# FilterBoard_Schematic.net
KiCad netlist of a schematic drawn in Altium Designer
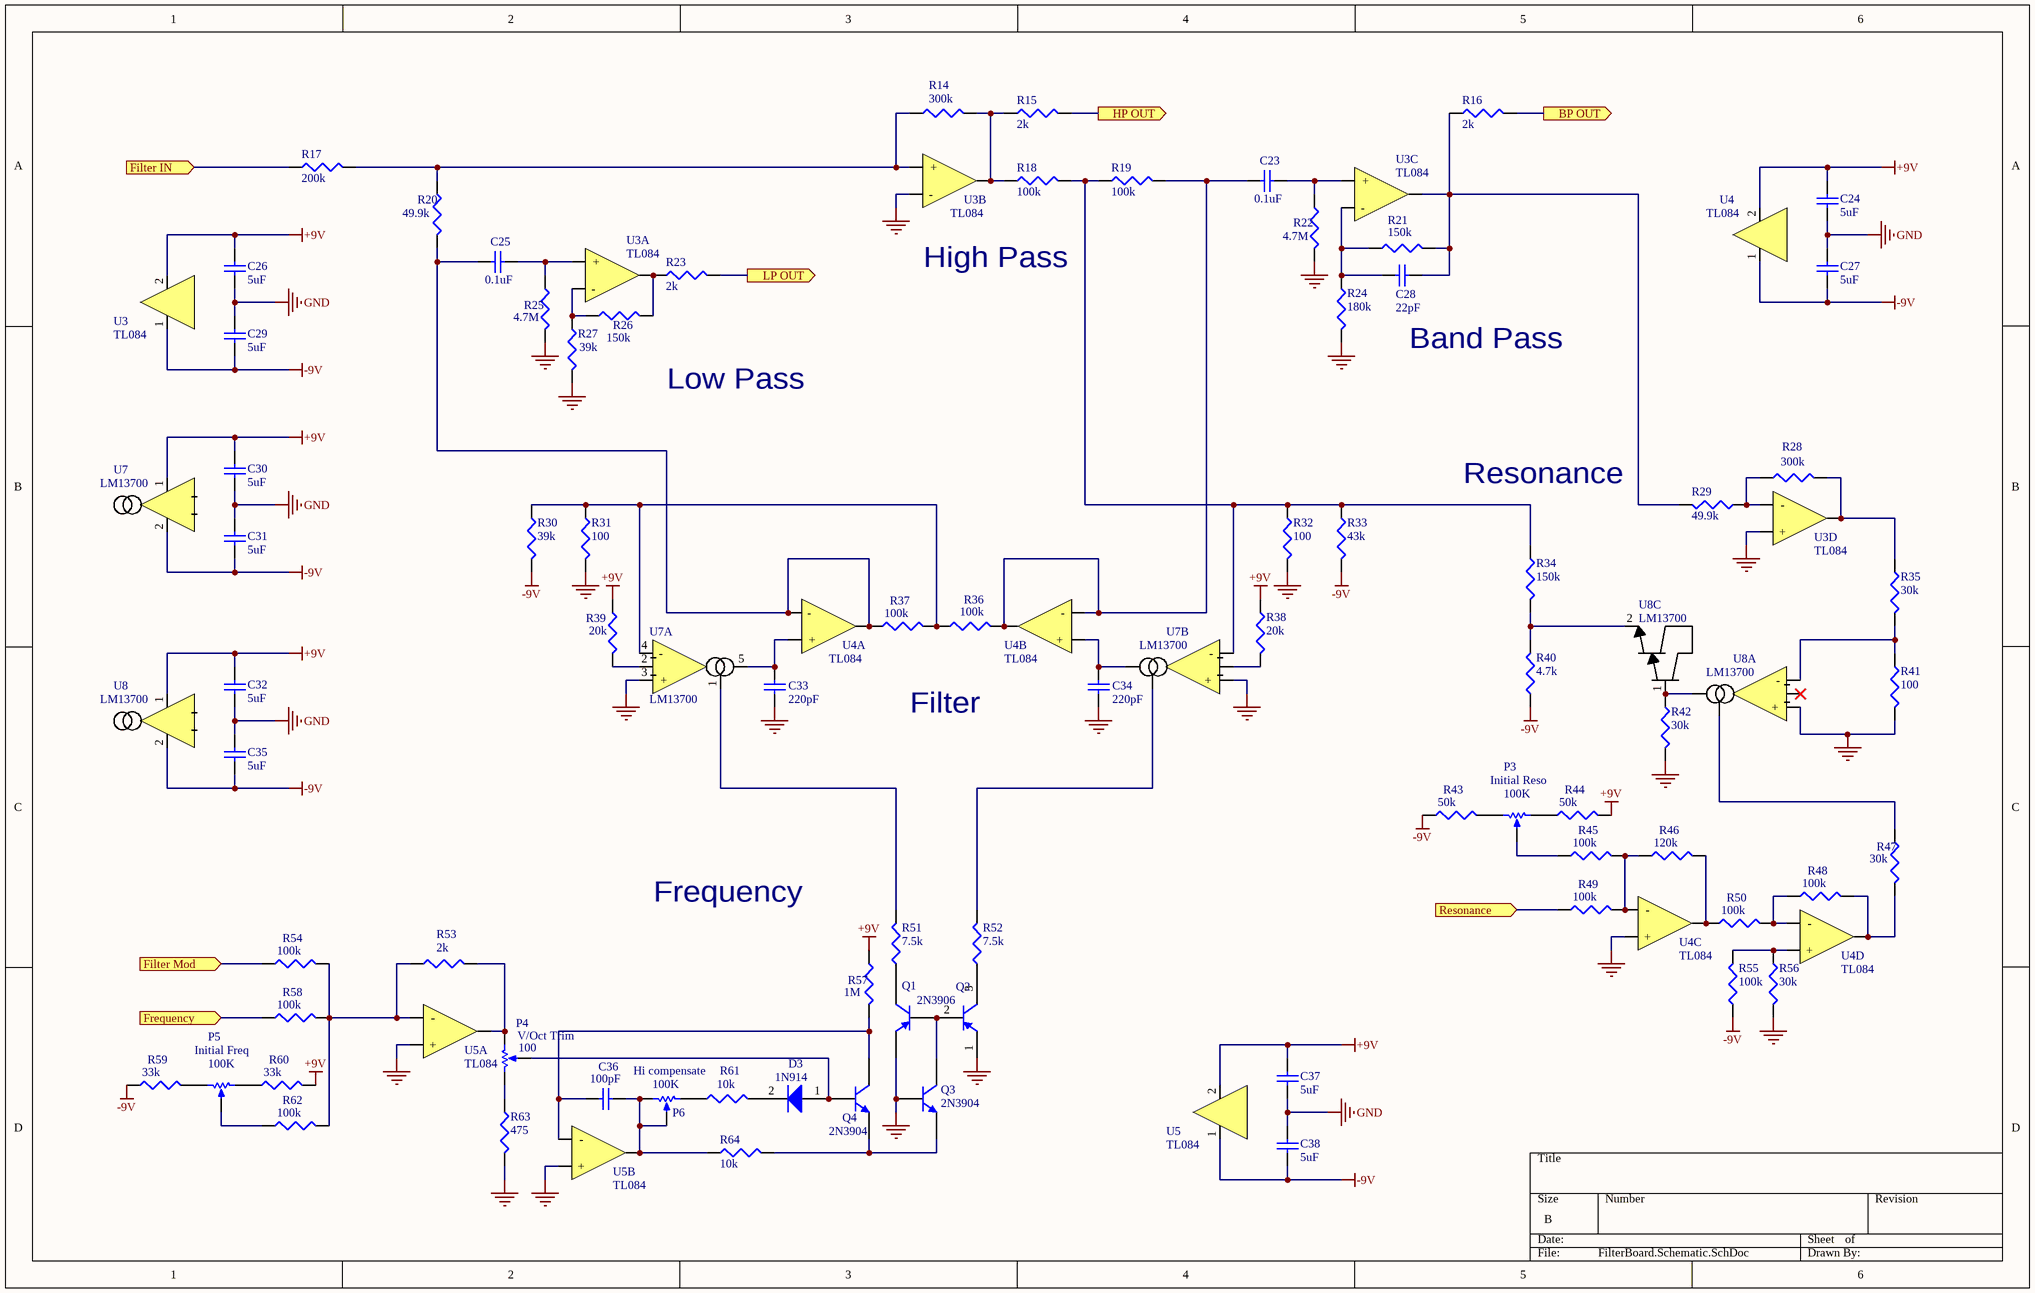
[diagram p0: FilterBoard.Schematic.SchDoc]

(export (version "E")
  (design (tool "Eeschema 10.0.6"))
  (components
    (comp (ref "C23")
      (value "0.1uF")
      (footprint "CAPC1608N - cap")
      (description "Capacitor (Semiconductor SIM Model)")
      (fields (field (name "PUBLISHER") "Altium Limited"))
      (libsource (lib "Miscellaneous Devices") (part "Cap Semi"))
    )
    (comp (ref "C24")
      (value "5uF")
      (footprint "CAPC1608N - cap")
      (description "Capacitor (Semiconductor SIM Model)")
      (fields (field (name "PUBLISHER") "Altium Limited"))
      (libsource (lib "Miscellaneous Devices") (part "Cap Semi"))
    )
    (comp (ref "C25")
      (value "0.1uF")
      (footprint "CAPC1608N - cap")
      (description "Capacitor (Semiconductor SIM Model)")
      (fields (field (name "PUBLISHER") "Altium Limited"))
      (libsource (lib "Miscellaneous Devices") (part "Cap Semi"))
    )
    (comp (ref "C26")
      (value "5uF")
      (footprint "CAPC1608N - cap")
      (description "Capacitor (Semiconductor SIM Model)")
      (fields (field (name "PUBLISHER") "Altium Limited"))
      (libsource (lib "Miscellaneous Devices") (part "Cap Semi"))
    )
    (comp (ref "C27")
      (value "5uF")
      (footprint "CAPC1608N - cap")
      (description "Capacitor (Semiconductor SIM Model)")
      (fields (field (name "PUBLISHER") "Altium Limited"))
      (libsource (lib "Miscellaneous Devices") (part "Cap Semi"))
    )
    (comp (ref "C28")
      (value "22pF")
      (footprint "CAPC1608N - cap")
      (description "Capacitor (Semiconductor SIM Model)")
      (fields (field (name "PUBLISHER") "Altium Limited"))
      (libsource (lib "Miscellaneous Devices") (part "Cap Semi"))
    )
    (comp (ref "C29")
      (value "5uF")
      (footprint "CAPC1608N - cap")
      (description "Capacitor (Semiconductor SIM Model)")
      (fields (field (name "PUBLISHER") "Altium Limited"))
      (libsource (lib "Miscellaneous Devices") (part "Cap Semi"))
    )
    (comp (ref "C30")
      (value "5uF")
      (footprint "CAPC1608N - cap")
      (description "Capacitor (Semiconductor SIM Model)")
      (fields (field (name "PUBLISHER") "Altium Limited"))
      (libsource (lib "Miscellaneous Devices") (part "Cap Semi"))
    )
    (comp (ref "C31")
      (value "5uF")
      (footprint "CAPC1608N - cap")
      (description "Capacitor (Semiconductor SIM Model)")
      (fields (field (name "PUBLISHER") "Altium Limited"))
      (libsource (lib "Miscellaneous Devices") (part "Cap Semi"))
    )
    (comp (ref "C32")
      (value "5uF")
      (footprint "CAPC1608N - cap")
      (description "Capacitor (Semiconductor SIM Model)")
      (fields (field (name "PUBLISHER") "Altium Limited"))
      (libsource (lib "Miscellaneous Devices") (part "Cap Semi"))
    )
    (comp (ref "C33")
      (value "220pF")
      (footprint "CAPC1608N - cap")
      (description "Capacitor (Semiconductor SIM Model)")
      (fields (field (name "PUBLISHER") "Altium Limited"))
      (libsource (lib "Miscellaneous Devices") (part "Cap Semi"))
    )
    (comp (ref "C34")
      (value "220pF")
      (footprint "CAPC1608N - cap")
      (description "Capacitor (Semiconductor SIM Model)")
      (fields (field (name "PUBLISHER") "Altium Limited"))
      (libsource (lib "Miscellaneous Devices") (part "Cap Semi"))
    )
    (comp (ref "C35")
      (value "5uF")
      (footprint "CAPC1608N - cap")
      (description "Capacitor (Semiconductor SIM Model)")
      (fields (field (name "PUBLISHER") "Altium Limited"))
      (libsource (lib "Miscellaneous Devices") (part "Cap Semi"))
    )
    (comp (ref "C36")
      (value "100pF")
      (footprint "CAPC1608N - cap")
      (description "Capacitor (Semiconductor SIM Model)")
      (fields (field (name "PUBLISHER") "Altium Limited"))
      (libsource (lib "Miscellaneous Devices") (part "Cap Semi"))
    )
    (comp (ref "C37")
      (value "5uF")
      (footprint "CAPC1608N - cap")
      (description "Capacitor (Semiconductor SIM Model)")
      (fields (field (name "PUBLISHER") "Altium Limited"))
      (libsource (lib "Miscellaneous Devices") (part "Cap Semi"))
    )
    (comp (ref "C38")
      (value "5uF")
      (footprint "CAPC1608N - cap")
      (description "Capacitor (Semiconductor SIM Model)")
      (fields (field (name "PUBLISHER") "Altium Limited"))
      (libsource (lib "Miscellaneous Devices") (part "Cap Semi"))
    )
    (comp (ref "D3")
      (value "1N914")
      (footprint "1N914")
      (description "1 Amp General Purpose Rectifier")
      (fields (field (name "PUBLISHER") "Altium Limited"))
      (libsource (lib "Miscellaneous Devices") (part "Diode 1N4001"))
    )
    (comp (ref "P3")
      (value "Initial Reso")
      (footprint "BOURNS Trim pot")
      (description "Potentiometer")
      (fields (field (name "ALTIUM_VALUE") "100K") (field (name "PUBLISHER") "Altium Limited"))
      (libsource (lib "Miscellaneous Devices") (part "RPot"))
    )
    (comp (ref "P4")
      (value "V/Oct Trim")
      (footprint "BOURNS Trim pot")
      (description "Potentiometer")
      (fields (field (name "ALTIUM_VALUE") "100") (field (name "PUBLISHER") "Altium Limited"))
      (libsource (lib "Miscellaneous Devices") (part "RPot"))
    )
    (comp (ref "P5")
      (value "Initial Freq")
      (footprint "BOURNS Trim pot")
      (description "Potentiometer")
      (fields (field (name "ALTIUM_VALUE") "100K") (field (name "PUBLISHER") "Altium Limited"))
      (libsource (lib "Miscellaneous Devices") (part "RPot"))
    )
    (comp (ref "P6")
      (value "Hi compensate")
      (footprint "BOURNS Trim pot")
      (description "Potentiometer")
      (fields (field (name "ALTIUM_VALUE") "100K") (field (name "PUBLISHER") "Altium Limited"))
      (libsource (lib "Miscellaneous Devices") (part "RPot"))
    )
    (comp (ref "Q1")
      (value "2N3906")
      (footprint "2N3906")
      (description "PNP General Purpose Amplifier")
      (fields (field (name "PUBLISHER") "Altium Limited"))
      (libsource (lib "") (part "2N3906_1"))
    )
    (comp (ref "Q2")
      (value "2N3906")
      (footprint "2N3906")
      (description "PNP General Purpose Amplifier")
      (fields (field (name "PUBLISHER") "Altium Limited"))
      (libsource (lib "Miscellaneous Devices") (part "2N3906"))
    )
    (comp (ref "Q3")
      (value "2N3904")
      (footprint "2N3906")
      (description "NPN General Purpose Amplifier")
      (fields (field (name "PUBLISHER") "Altium Limited"))
      (libsource (lib "Miscellaneous Devices") (part "2N3904"))
    )
    (comp (ref "Q4")
      (value "2N3904")
      (footprint "2N3906")
      (description "NPN General Purpose Amplifier")
      (fields (field (name "PUBLISHER") "Altium Limited"))
      (libsource (lib "Miscellaneous Devices") (part "2N3904"))
    )
    (comp (ref "R14")
      (value "300k")
      (footprint "CAPC1608N")
      (description "Resistor")
      (fields (field (name "PUBLISHER") "Altium Limited"))
      (libsource (lib "Miscellaneous Devices") (part "Res3"))
    )
    (comp (ref "R15")
      (value "2k")
      (footprint "CAPC1608N")
      (description "Resistor")
      (fields (field (name "PUBLISHER") "Altium Limited"))
      (libsource (lib "Miscellaneous Devices") (part "Res3"))
    )
    (comp (ref "R16")
      (value "2k")
      (footprint "CAPC1608N")
      (description "Resistor")
      (fields (field (name "PUBLISHER") "Altium Limited"))
      (libsource (lib "Miscellaneous Devices") (part "Res3"))
    )
    (comp (ref "R17")
      (value "200k")
      (footprint "CAPC1608N")
      (description "Resistor")
      (fields (field (name "PUBLISHER") "Altium Limited"))
      (libsource (lib "Miscellaneous Devices") (part "Res3"))
    )
    (comp (ref "R18")
      (value "100k")
      (footprint "CAPC1608N")
      (description "Resistor")
      (fields (field (name "PUBLISHER") "Altium Limited"))
      (libsource (lib "Miscellaneous Devices") (part "Res3"))
    )
    (comp (ref "R19")
      (value "100k")
      (footprint "CAPC1608N")
      (description "Resistor")
      (fields (field (name "PUBLISHER") "Altium Limited"))
      (libsource (lib "Miscellaneous Devices") (part "Res3"))
    )
    (comp (ref "R20")
      (value "49.9k")
      (footprint "CAPC1608N")
      (description "Resistor")
      (fields (field (name "PUBLISHER") "Altium Limited"))
      (libsource (lib "Miscellaneous Devices") (part "Res3"))
    )
    (comp (ref "R21")
      (value "150k")
      (footprint "CAPC1608N")
      (description "Resistor")
      (fields (field (name "PUBLISHER") "Altium Limited"))
      (libsource (lib "Miscellaneous Devices") (part "Res3"))
    )
    (comp (ref "R22")
      (value "4.7M")
      (footprint "CAPC1608N")
      (description "Resistor")
      (fields (field (name "PUBLISHER") "Altium Limited"))
      (libsource (lib "Miscellaneous Devices") (part "Res3"))
    )
    (comp (ref "R23")
      (value "2k")
      (footprint "CAPC1608N")
      (description "Resistor")
      (fields (field (name "PUBLISHER") "Altium Limited"))
      (libsource (lib "Miscellaneous Devices") (part "Res3"))
    )
    (comp (ref "R24")
      (value "180k")
      (footprint "CAPC1608N")
      (description "Resistor")
      (fields (field (name "PUBLISHER") "Altium Limited"))
      (libsource (lib "Miscellaneous Devices") (part "Res3"))
    )
    (comp (ref "R25")
      (value "4.7M")
      (footprint "CAPC1608N")
      (description "Resistor")
      (fields (field (name "PUBLISHER") "Altium Limited"))
      (libsource (lib "Miscellaneous Devices") (part "Res3"))
    )
    (comp (ref "R26")
      (value "150k")
      (footprint "CAPC1608N")
      (description "Resistor")
      (fields (field (name "PUBLISHER") "Altium Limited"))
      (libsource (lib "Miscellaneous Devices") (part "Res3"))
    )
    (comp (ref "R27")
      (value "39k")
      (footprint "CAPC1608N")
      (description "Resistor")
      (fields (field (name "PUBLISHER") "Altium Limited"))
      (libsource (lib "Miscellaneous Devices") (part "Res3"))
    )
    (comp (ref "R28")
      (value "300k")
      (footprint "CAPC1608N")
      (description "Resistor")
      (fields (field (name "PUBLISHER") "Altium Limited"))
      (libsource (lib "Miscellaneous Devices") (part "Res3"))
    )
    (comp (ref "R29")
      (value "49.9k")
      (footprint "CAPC1608N")
      (description "Resistor")
      (fields (field (name "PUBLISHER") "Altium Limited"))
      (libsource (lib "Miscellaneous Devices") (part "Res3"))
    )
    (comp (ref "R30")
      (value "39k")
      (footprint "CAPC1608N")
      (description "Resistor")
      (fields (field (name "PUBLISHER") "Altium Limited"))
      (libsource (lib "Miscellaneous Devices") (part "Res3"))
    )
    (comp (ref "R31")
      (value "100")
      (footprint "CAPC1608N")
      (description "Resistor")
      (fields (field (name "PUBLISHER") "Altium Limited"))
      (libsource (lib "Miscellaneous Devices") (part "Res3"))
    )
    (comp (ref "R32")
      (value "100")
      (footprint "CAPC1608N")
      (description "Resistor")
      (fields (field (name "PUBLISHER") "Altium Limited"))
      (libsource (lib "Miscellaneous Devices") (part "Res3"))
    )
    (comp (ref "R33")
      (value "43k")
      (footprint "CAPC1608N")
      (description "Resistor")
      (fields (field (name "PUBLISHER") "Altium Limited"))
      (libsource (lib "Miscellaneous Devices") (part "Res3"))
    )
    (comp (ref "R34")
      (value "150k")
      (footprint "CAPC1608N")
      (description "Resistor")
      (fields (field (name "PUBLISHER") "Altium Limited"))
      (libsource (lib "Miscellaneous Devices") (part "Res3"))
    )
    (comp (ref "R35")
      (value "30k")
      (footprint "CAPC1608N")
      (description "Resistor")
      (fields (field (name "PUBLISHER") "Altium Limited"))
      (libsource (lib "Miscellaneous Devices") (part "Res3"))
    )
    (comp (ref "R36")
      (value "100k")
      (footprint "CAPC1608N")
      (description "Resistor")
      (fields (field (name "PUBLISHER") "Altium Limited"))
      (libsource (lib "Miscellaneous Devices") (part "Res3"))
    )
    (comp (ref "R37")
      (value "100k")
      (footprint "CAPC1608N")
      (description "Resistor")
      (fields (field (name "PUBLISHER") "Altium Limited"))
      (libsource (lib "Miscellaneous Devices") (part "Res3"))
    )
    (comp (ref "R38")
      (value "20k")
      (footprint "CAPC1608N")
      (description "Resistor")
      (fields (field (name "PUBLISHER") "Altium Limited"))
      (libsource (lib "Miscellaneous Devices") (part "Res3"))
    )
    (comp (ref "R39")
      (value "20k")
      (footprint "CAPC1608N")
      (description "Resistor")
      (fields (field (name "PUBLISHER") "Altium Limited"))
      (libsource (lib "Miscellaneous Devices") (part "Res3"))
    )
    (comp (ref "R40")
      (value "4.7k")
      (footprint "CAPC1608N")
      (description "Resistor")
      (fields (field (name "PUBLISHER") "Altium Limited"))
      (libsource (lib "Miscellaneous Devices") (part "Res3"))
    )
    (comp (ref "R41")
      (value "100")
      (footprint "CAPC1608N")
      (description "Resistor")
      (fields (field (name "PUBLISHER") "Altium Limited"))
      (libsource (lib "Miscellaneous Devices") (part "Res3"))
    )
    (comp (ref "R42")
      (value "30k")
      (footprint "CAPC1608N")
      (description "Resistor")
      (fields (field (name "PUBLISHER") "Altium Limited"))
      (libsource (lib "Miscellaneous Devices") (part "Res3"))
    )
    (comp (ref "R43")
      (value "50k")
      (footprint "CAPC1608N")
      (description "Resistor")
      (fields (field (name "PUBLISHER") "Altium Limited"))
      (libsource (lib "Miscellaneous Devices") (part "Res3"))
    )
    (comp (ref "R44")
      (value "50k")
      (footprint "CAPC1608N")
      (description "Resistor")
      (fields (field (name "PUBLISHER") "Altium Limited"))
      (libsource (lib "Miscellaneous Devices") (part "Res3"))
    )
    (comp (ref "R45")
      (value "100k")
      (footprint "CAPC1608N")
      (description "Resistor")
      (fields (field (name "PUBLISHER") "Altium Limited"))
      (libsource (lib "Miscellaneous Devices") (part "Res3"))
    )
    (comp (ref "R46")
      (value "120k")
      (footprint "CAPC1608N")
      (description "Resistor")
      (fields (field (name "PUBLISHER") "Altium Limited"))
      (libsource (lib "Miscellaneous Devices") (part "Res3"))
    )
    (comp (ref "R47")
      (value "30k")
      (footprint "CAPC1608N")
      (description "Resistor")
      (fields (field (name "PUBLISHER") "Altium Limited"))
      (libsource (lib "Miscellaneous Devices") (part "Res3"))
    )
    (comp (ref "R48")
      (value "100k")
      (footprint "CAPC1608N")
      (description "Resistor")
      (fields (field (name "PUBLISHER") "Altium Limited"))
      (libsource (lib "Miscellaneous Devices") (part "Res3"))
    )
    (comp (ref "R49")
      (value "100k")
      (footprint "CAPC1608N")
      (description "Resistor")
      (fields (field (name "PUBLISHER") "Altium Limited"))
      (libsource (lib "Miscellaneous Devices") (part "Res3"))
    )
    (comp (ref "R50")
      (value "100k")
      (footprint "CAPC1608N")
      (description "Resistor")
      (fields (field (name "PUBLISHER") "Altium Limited"))
      (libsource (lib "Miscellaneous Devices") (part "Res3"))
    )
    (comp (ref "R51")
      (value "7.5k")
      (footprint "CAPC1608N")
      (description "Resistor")
      (fields (field (name "PUBLISHER") "Altium Limited"))
      (libsource (lib "Miscellaneous Devices") (part "Res3"))
    )
    (comp (ref "R52")
      (value "7.5k")
      (footprint "CAPC1608N")
      (description "Resistor")
      (fields (field (name "PUBLISHER") "Altium Limited"))
      (libsource (lib "Miscellaneous Devices") (part "Res3"))
    )
    (comp (ref "R53")
      (value "2k")
      (footprint "CAPC1608N")
      (description "Resistor")
      (fields (field (name "PUBLISHER") "Altium Limited"))
      (libsource (lib "Miscellaneous Devices") (part "Res3"))
    )
    (comp (ref "R54")
      (value "100k")
      (footprint "CAPC1608N")
      (description "Resistor")
      (fields (field (name "PUBLISHER") "Altium Limited"))
      (libsource (lib "Miscellaneous Devices") (part "Res3"))
    )
    (comp (ref "R55")
      (value "100k")
      (footprint "CAPC1608N")
      (description "Resistor")
      (fields (field (name "PUBLISHER") "Altium Limited"))
      (libsource (lib "Miscellaneous Devices") (part "Res3"))
    )
    (comp (ref "R56")
      (value "30k")
      (footprint "CAPC1608N")
      (description "Resistor")
      (fields (field (name "PUBLISHER") "Altium Limited"))
      (libsource (lib "Miscellaneous Devices") (part "Res3"))
    )
    (comp (ref "R57")
      (value "1M")
      (footprint "CAPC1608N")
      (description "Resistor")
      (fields (field (name "PUBLISHER") "Altium Limited"))
      (libsource (lib "Miscellaneous Devices") (part "Res3"))
    )
    (comp (ref "R58")
      (value "100k")
      (footprint "CAPC1608N")
      (description "Resistor")
      (fields (field (name "PUBLISHER") "Altium Limited"))
      (libsource (lib "Miscellaneous Devices") (part "Res3"))
    )
    (comp (ref "R59")
      (value "33k")
      (footprint "CAPC1608N")
      (description "Resistor")
      (fields (field (name "PUBLISHER") "Altium Limited"))
      (libsource (lib "Miscellaneous Devices") (part "Res3"))
    )
    (comp (ref "R60")
      (value "33k")
      (footprint "CAPC1608N")
      (description "Resistor")
      (fields (field (name "PUBLISHER") "Altium Limited"))
      (libsource (lib "Miscellaneous Devices") (part "Res3"))
    )
    (comp (ref "R61")
      (value "10k")
      (footprint "CAPC1608N")
      (description "Resistor")
      (fields (field (name "PUBLISHER") "Altium Limited"))
      (libsource (lib "Miscellaneous Devices") (part "Res3"))
    )
    (comp (ref "R62")
      (value "100k")
      (footprint "CAPC1608N")
      (description "Resistor")
      (fields (field (name "PUBLISHER") "Altium Limited"))
      (libsource (lib "Miscellaneous Devices") (part "Res3"))
    )
    (comp (ref "R63")
      (value "475")
      (footprint "CAPC1608N")
      (description "Resistor")
      (fields (field (name "PUBLISHER") "Altium Limited"))
      (libsource (lib "Miscellaneous Devices") (part "Res3"))
    )
    (comp (ref "R64")
      (value "10k")
      (footprint "CAPC1608N")
      (description "Resistor")
      (fields (field (name "PUBLISHER") "Altium Limited"))
      (libsource (lib "Miscellaneous Devices") (part "Res3"))
    )
    (comp (ref "U3")
      (value "TL084")
      (footprint "TL084 - Alim")
      (libsource (lib "SynthyTwo.Components") (part "TL_CLEAN"))
    )
    (comp (ref "U3A") (value "TL084") (footprint "TL084 - 3pads") (libsource (lib "") (part "TL084_1")))
    (comp (ref "U3B") (value "TL084") (footprint "TL084 - 3pads") (libsource (lib "") (part "TL084_1")))
    (comp (ref "U3C") (value "TL084") (footprint "TL084 - 3pads") (libsource (lib "") (part "TL084_1")))
    (comp (ref "U3D")
      (value "TL084")
      (footprint "TL084 - 3pads")
      (libsource (lib "SynthyTwo.Components") (part "TL084"))
    )
    (comp (ref "U4")
      (value "TL084")
      (footprint "TL084 - Alim")
      (libsource (lib "SynthyTwo.Components") (part "TL_CLEAN"))
    )
    (comp (ref "U4A") (value "TL084") (footprint "TL084 - 3pads") (libsource (lib "") (part "TL084_1")))
    (comp (ref "U4B") (value "TL084") (footprint "TL084 - 3pads") (libsource (lib "") (part "TL084_1")))
    (comp (ref "U4C")
      (value "TL084")
      (footprint "TL084 - 3pads")
      (libsource (lib "SynthyTwo.Components") (part "TL084"))
    )
    (comp (ref "U4D")
      (value "TL084")
      (footprint "TL084 - 3pads")
      (libsource (lib "SynthyTwo.Components") (part "TL084"))
    )
    (comp (ref "U5")
      (value "TL084")
      (footprint "TL084 - Alim")
      (libsource (lib "SynthyTwo.Components") (part "TL_CLEAN"))
    )
    (comp (ref "U5A")
      (value "TL084")
      (footprint "TL084 - 3pads")
      (libsource (lib "SynthyTwo.Components") (part "TL084"))
    )
    (comp (ref "U5B")
      (value "TL084")
      (footprint "TL084 - 3pads")
      (libsource (lib "SynthyTwo.Components") (part "TL084"))
    )
    (comp (ref "U7")
      (value "LM13700")
      (footprint "LM13700 - Alim")
      (libsource (lib "SynthyTwo.Components") (part "LM13700"))
    )
    (comp (ref "U7A")
      (value "LM13700")
      (footprint "LM13700 - A")
      (libsource (lib "SynthyTwo.Components") (part "LM13700_2"))
    )
    (comp (ref "U7B") (value "LM13700") (footprint "LM13700 - B") (libsource (lib "") (part "LM13700_2_1")))
    (comp (ref "U8")
      (value "LM13700")
      (footprint "LM13700 - Alim")
      (libsource (lib "SynthyTwo.Components") (part "LM13700"))
    )
    (comp (ref "U8A") (value "LM13700") (footprint "LM13700 - A") (libsource (lib "") (part "LM13700_2_1")))
    (comp (ref "U8C")
      (value "LM13700")
      (footprint "LM13700 - C")
      (libsource (lib "SynthyTwo.Components") (part "LM13700_1"))
    )
  )
  (nets
    (net (code "1") (name "+9V") (class "Default")
      (node (ref "C24") (pin "1") (pinfunction "1_1") (pintype "passive"))
      (node (ref "C26") (pin "1") (pinfunction "1_1") (pintype "passive"))
      (node (ref "C30") (pin "1") (pinfunction "1_1") (pintype "passive"))
      (node (ref "C32") (pin "1") (pinfunction "1_1") (pintype "passive"))
      (node (ref "C37") (pin "1") (pinfunction "1_1") (pintype "passive"))
      (node (ref "R38") (pin "1") (pinfunction "1_1") (pintype "passive"))
      (node (ref "R39") (pin "1") (pinfunction "1_1") (pintype "passive"))
      (node (ref "R44") (pin "2") (pinfunction "2_2") (pintype "passive"))
      (node (ref "R57") (pin "1") (pinfunction "1_1") (pintype "passive"))
      (node (ref "R60") (pin "2") (pinfunction "2_2") (pintype "passive"))
      (node (ref "U3") (pin "2") (pinfunction "VCC-_2") (pintype "passive"))
      (node (ref "U4") (pin "2") (pinfunction "VCC-_2") (pintype "passive"))
      (node (ref "U5") (pin "2") (pinfunction "VCC-_2") (pintype "passive"))
      (node (ref "U7") (pin "1") (pinfunction "VCC-_1") (pintype "passive"))
      (node (ref "U8") (pin "1") (pinfunction "VCC-_1") (pintype "passive"))
    )
    (net (code "2") (name "-9V") (class "Default")
      (node (ref "C27") (pin "2") (pinfunction "2_2") (pintype "passive"))
      (node (ref "C29") (pin "2") (pinfunction "2_2") (pintype "passive"))
      (node (ref "C31") (pin "2") (pinfunction "2_2") (pintype "passive"))
      (node (ref "C35") (pin "2") (pinfunction "2_2") (pintype "passive"))
      (node (ref "C38") (pin "2") (pinfunction "2_2") (pintype "passive"))
      (node (ref "R30") (pin "2") (pinfunction "2_2") (pintype "passive"))
      (node (ref "R33") (pin "2") (pinfunction "2_2") (pintype "passive"))
      (node (ref "R40") (pin "1") (pinfunction "1_1") (pintype "passive"))
      (node (ref "R43") (pin "1") (pinfunction "1_1") (pintype "passive"))
      (node (ref "R55") (pin "1") (pinfunction "1_1") (pintype "passive"))
      (node (ref "R59") (pin "1") (pinfunction "1_1") (pintype "passive"))
      (node (ref "U3") (pin "1") (pinfunction "VCC+_1") (pintype "passive"))
      (node (ref "U4") (pin "1") (pinfunction "VCC+_1") (pintype "passive"))
      (node (ref "U5") (pin "1") (pinfunction "VCC+_1") (pintype "passive"))
      (node (ref "U7") (pin "2") (pinfunction "VCC-_2") (pintype "passive"))
      (node (ref "U8") (pin "2") (pinfunction "VCC-_2") (pintype "passive"))
    )
    (net (code "3") (name "/BP OUT") (class "Default")
      (node (ref "R16") (pin "2") (pinfunction "2_2") (pintype "passive"))
    )
    (net (code "4") (name "/Filter IN") (class "Default")
      (node (ref "R17") (pin "1") (pinfunction "1_1") (pintype "passive"))
    )
    (net (code "5") (name "/Filter Mod") (class "Default")
      (node (ref "R54") (pin "1") (pinfunction "1_1") (pintype "passive"))
    )
    (net (code "6") (name "/Frequency") (class "Default")
      (node (ref "R58") (pin "1") (pinfunction "1_1") (pintype "passive"))
    )
    (net (code "7") (name "/HP OUT") (class "Default")
      (node (ref "R15") (pin "2") (pinfunction "2_2") (pintype "passive"))
    )
    (net (code "8") (name "/LP OUT") (class "Default")
      (node (ref "R23") (pin "2") (pinfunction "2_2") (pintype "passive"))
    )
    (net (code "9") (name "/Resonance") (class "Default")
      (node (ref "R49") (pin "1") (pinfunction "1_1") (pintype "passive"))
    )
    (net (code "10") (name "GND") (class "Default")
      (node (ref "C24") (pin "2") (pinfunction "2_2") (pintype "passive"))
      (node (ref "C26") (pin "2") (pinfunction "2_2") (pintype "passive"))
      (node (ref "C27") (pin "1") (pinfunction "1_1") (pintype "passive"))
      (node (ref "C29") (pin "1") (pinfunction "1_1") (pintype "passive"))
      (node (ref "C30") (pin "2") (pinfunction "2_2") (pintype "passive"))
      (node (ref "C31") (pin "1") (pinfunction "1_1") (pintype "passive"))
      (node (ref "C32") (pin "2") (pinfunction "2_2") (pintype "passive"))
      (node (ref "C33") (pin "1") (pinfunction "1_1") (pintype "passive"))
      (node (ref "C34") (pin "1") (pinfunction "1_1") (pintype "passive"))
      (node (ref "C35") (pin "1") (pinfunction "1_1") (pintype "passive"))
      (node (ref "C37") (pin "2") (pinfunction "2_2") (pintype "passive"))
      (node (ref "C38") (pin "1") (pinfunction "1_1") (pintype "passive"))
      (node (ref "Q1") (pin "1") (pinfunction "E_1") (pintype "passive"))
      (node (ref "Q2") (pin "1") (pinfunction "E_1") (pintype "passive"))
      (node (ref "Q3") (pin "2") (pinfunction "B_2") (pintype "passive"))
      (node (ref "R22") (pin "2") (pinfunction "2_2") (pintype "passive"))
      (node (ref "R24") (pin "2") (pinfunction "2_2") (pintype "passive"))
      (node (ref "R25") (pin "2") (pinfunction "2_2") (pintype "passive"))
      (node (ref "R27") (pin "2") (pinfunction "2_2") (pintype "passive"))
      (node (ref "R31") (pin "2") (pinfunction "2_2") (pintype "passive"))
      (node (ref "R32") (pin "2") (pinfunction "2_2") (pintype "passive"))
      (node (ref "R41") (pin "2") (pinfunction "2_2") (pintype "passive"))
      (node (ref "R42") (pin "2") (pinfunction "2_2") (pintype "passive"))
      (node (ref "R56") (pin "2") (pinfunction "2_2") (pintype "passive"))
      (node (ref "R63") (pin "2") (pinfunction "2_2") (pintype "passive"))
      (node (ref "U3B") (pin "2") (pinfunction "-_2") (pintype "passive"))
      (node (ref "U3D") (pin "3") (pinfunction "+_3") (pintype "passive"))
      (node (ref "U4C") (pin "3") (pinfunction "+_3") (pintype "passive"))
      (node (ref "U5A") (pin "3") (pinfunction "+_3") (pintype "passive"))
      (node (ref "U5B") (pin "3") (pinfunction "+_3") (pintype "passive"))
      (node (ref "U7A") (pin "3") (pinfunction "+_3") (pintype "passive"))
      (node (ref "U7B") (pin "3") (pinfunction "+_3") (pintype "passive"))
      (node (ref "U8A") (pin "3") (pinfunction "+_3") (pintype "passive"))
    )
    (net (code "11") (name "Net-(D3-A)") (class "Default")
      (node (ref "D3") (pin "1") (pinfunction "A_1") (pintype "passive"))
      (node (ref "P4") (pin "3") (pinfunction "TAP_3") (pintype "passive"))
      (node (ref "Q4") (pin "2") (pinfunction "B_2") (pintype "passive"))
    )
    (net (code "12") (name "Net-(D3-K)") (class "Default")
      (node (ref "D3") (pin "2") (pinfunction "K_2") (pintype "passive"))
      (node (ref "R61") (pin "2") (pinfunction "2_2") (pintype "passive"))
    )
    (net (code "13") (name "Net-(P3-BOT)") (class "Default")
      (node (ref "P3") (pin "2") (pinfunction "BOT_2") (pintype "passive"))
      (node (ref "R43") (pin "2") (pinfunction "2_2") (pintype "passive"))
    )
    (net (code "14") (name "Net-(P3-TAP)") (class "Default")
      (node (ref "P3") (pin "3") (pinfunction "TAP_3") (pintype "passive"))
      (node (ref "R45") (pin "1") (pinfunction "1_1") (pintype "passive"))
    )
    (net (code "15") (name "Net-(P3-TOP)") (class "Default")
      (node (ref "P3") (pin "1") (pinfunction "TOP_1") (pintype "passive"))
      (node (ref "R44") (pin "1") (pinfunction "1_1") (pintype "passive"))
    )
    (net (code "16") (name "Net-(P4-BOT)") (class "Default")
      (node (ref "P4") (pin "2") (pinfunction "BOT_2") (pintype "passive"))
      (node (ref "R63") (pin "1") (pinfunction "1_1") (pintype "passive"))
    )
    (net (code "17") (name "Net-(P4-TOP)") (class "Default")
      (node (ref "P4") (pin "1") (pinfunction "TOP_1") (pintype "passive"))
      (node (ref "R53") (pin "2") (pinfunction "2_2") (pintype "passive"))
      (node (ref "U5A") (pin "1") (pinfunction "OUT_1") (pintype "passive"))
    )
    (net (code "18") (name "Net-(P5-BOT)") (class "Default")
      (node (ref "P5") (pin "2") (pinfunction "BOT_2") (pintype "passive"))
      (node (ref "R59") (pin "2") (pinfunction "2_2") (pintype "passive"))
    )
    (net (code "19") (name "Net-(P5-TAP)") (class "Default")
      (node (ref "P5") (pin "3") (pinfunction "TAP_3") (pintype "passive"))
      (node (ref "R62") (pin "1") (pinfunction "1_1") (pintype "passive"))
    )
    (net (code "20") (name "Net-(P5-TOP)") (class "Default")
      (node (ref "P5") (pin "1") (pinfunction "TOP_1") (pintype "passive"))
      (node (ref "R60") (pin "1") (pinfunction "1_1") (pintype "passive"))
    )
    (net (code "21") (name "Net-(P6-BOT)") (class "Default")
      (node (ref "C36") (pin "2") (pinfunction "2_2") (pintype "passive"))
      (node (ref "P6") (pin "2") (pinfunction "BOT_2") (pintype "passive"))
      (node (ref "P6") (pin "3") (pinfunction "TAP_3") (pintype "passive"))
      (node (ref "R64") (pin "1") (pinfunction "1_1") (pintype "passive"))
      (node (ref "U5B") (pin "1") (pinfunction "OUT_1") (pintype "passive"))
    )
    (net (code "22") (name "Net-(P6-TOP)") (class "Default")
      (node (ref "P6") (pin "1") (pinfunction "TOP_1") (pintype "passive"))
      (node (ref "R61") (pin "1") (pinfunction "1_1") (pintype "passive"))
    )
    (net (code "23") (name "Net-(Q1-B)") (class "Default")
      (node (ref "Q1") (pin "2") (pinfunction "B_2") (pintype "passive"))
      (node (ref "Q2") (pin "2") (pinfunction "B_2") (pintype "passive"))
      (node (ref "Q3") (pin "3") (pinfunction "C_3") (pintype "passive"))
    )
    (net (code "24") (name "Net-(Q1-C)") (class "Default")
      (node (ref "Q1") (pin "3") (pinfunction "C_3") (pintype "passive"))
      (node (ref "R51") (pin "1") (pinfunction "1_1") (pintype "passive"))
    )
    (net (code "25") (name "Net-(Q2-C)") (class "Default")
      (node (ref "Q2") (pin "3") (pinfunction "C_3") (pintype "passive"))
      (node (ref "R52") (pin "1") (pinfunction "1_1") (pintype "passive"))
    )
    (net (code "26") (name "Net-(Q3-E)") (class "Default")
      (node (ref "Q3") (pin "1") (pinfunction "E_1") (pintype "passive"))
      (node (ref "Q4") (pin "1") (pinfunction "E_1") (pintype "passive"))
      (node (ref "R64") (pin "2") (pinfunction "2_2") (pintype "passive"))
    )
    (net (code "27") (name "Net-(Q4-C)") (class "Default")
      (node (ref "C36") (pin "1") (pinfunction "1_1") (pintype "passive"))
      (node (ref "Q4") (pin "3") (pinfunction "C_3") (pintype "passive"))
      (node (ref "R57") (pin "2") (pinfunction "2_2") (pintype "passive"))
      (node (ref "U5B") (pin "2") (pinfunction "-_2") (pintype "passive"))
    )
    (net (code "28") (name "Net-(R38-Pad2)") (class "Default")
      (node (ref "R38") (pin "2") (pinfunction "2_2") (pintype "passive"))
      (node (ref "U7B") (pin "2") (pinfunction "2_2") (pintype "passive"))
    )
    (net (code "29") (name "Net-(R39-Pad2)") (class "Default")
      (node (ref "R39") (pin "2") (pinfunction "2_2") (pintype "passive"))
      (node (ref "U7A") (pin "2") (pinfunction "2_2") (pintype "passive"))
    )
    (net (code "30") (name "Net-(U3A-+)") (class "Default")
      (node (ref "C25") (pin "2") (pinfunction "2_2") (pintype "passive"))
      (node (ref "R25") (pin "1") (pinfunction "1_1") (pintype "passive"))
      (node (ref "U3A") (pin "3") (pinfunction "+_3") (pintype "passive"))
    )
    (net (code "31") (name "Net-(U3A--)") (class "Default")
      (node (ref "R26") (pin "1") (pinfunction "1_1") (pintype "passive"))
      (node (ref "R27") (pin "1") (pinfunction "1_1") (pintype "passive"))
      (node (ref "U3A") (pin "2") (pinfunction "-_2") (pintype "passive"))
    )
    (net (code "32") (name "Net-(U3A-OUT)") (class "Default")
      (node (ref "R23") (pin "1") (pinfunction "1_1") (pintype "passive"))
      (node (ref "R26") (pin "2") (pinfunction "2_2") (pintype "passive"))
      (node (ref "U3A") (pin "1") (pinfunction "OUT_1") (pintype "passive"))
    )
    (net (code "33") (name "Net-(U3B-+)") (class "Default")
      (node (ref "R14") (pin "1") (pinfunction "1_1") (pintype "passive"))
      (node (ref "R17") (pin "2") (pinfunction "2_2") (pintype "passive"))
      (node (ref "R20") (pin "1") (pinfunction "1_1") (pintype "passive"))
      (node (ref "U3B") (pin "3") (pinfunction "+_3") (pintype "passive"))
    )
    (net (code "34") (name "Net-(U3B-OUT)") (class "Default")
      (node (ref "R14") (pin "2") (pinfunction "2_2") (pintype "passive"))
      (node (ref "R15") (pin "1") (pinfunction "1_1") (pintype "passive"))
      (node (ref "R18") (pin "1") (pinfunction "1_1") (pintype "passive"))
      (node (ref "U3B") (pin "1") (pinfunction "OUT_1") (pintype "passive"))
    )
    (net (code "35") (name "Net-(U3C-+)") (class "Default")
      (node (ref "C23") (pin "2") (pinfunction "2_2") (pintype "passive"))
      (node (ref "R22") (pin "1") (pinfunction "1_1") (pintype "passive"))
      (node (ref "U3C") (pin "3") (pinfunction "+_3") (pintype "passive"))
    )
    (net (code "36") (name "Net-(U3C--)") (class "Default")
      (node (ref "C28") (pin "1") (pinfunction "1_1") (pintype "passive"))
      (node (ref "R21") (pin "1") (pinfunction "1_1") (pintype "passive"))
      (node (ref "R24") (pin "1") (pinfunction "1_1") (pintype "passive"))
      (node (ref "U3C") (pin "2") (pinfunction "-_2") (pintype "passive"))
    )
    (net (code "37") (name "Net-(U3C-OUT)") (class "Default")
      (node (ref "C28") (pin "2") (pinfunction "2_2") (pintype "passive"))
      (node (ref "R16") (pin "1") (pinfunction "1_1") (pintype "passive"))
      (node (ref "R21") (pin "2") (pinfunction "2_2") (pintype "passive"))
      (node (ref "R29") (pin "2") (pinfunction "2_2") (pintype "passive"))
      (node (ref "U3C") (pin "1") (pinfunction "OUT_1") (pintype "passive"))
    )
    (net (code "38") (name "Net-(U3D--)") (class "Default")
      (node (ref "R28") (pin "1") (pinfunction "1_1") (pintype "passive"))
      (node (ref "R29") (pin "1") (pinfunction "1_1") (pintype "passive"))
      (node (ref "U3D") (pin "2") (pinfunction "-_2") (pintype "passive"))
    )
    (net (code "39") (name "Net-(U3D-OUT)") (class "Default")
      (node (ref "R28") (pin "2") (pinfunction "2_2") (pintype "passive"))
      (node (ref "R35") (pin "1") (pinfunction "1_1") (pintype "passive"))
      (node (ref "U3D") (pin "1") (pinfunction "OUT_1") (pintype "passive"))
    )
    (net (code "40") (name "Net-(U4A-+)") (class "Default")
      (node (ref "C33") (pin "2") (pinfunction "2_2") (pintype "passive"))
      (node (ref "U4A") (pin "3") (pinfunction "+_3") (pintype "passive"))
      (node (ref "U7A") (pin "5") (pinfunction "OUT_5") (pintype "passive"))
    )
    (net (code "41") (name "Net-(U4A--)") (class "Default")
      (node (ref "C25") (pin "1") (pinfunction "1_1") (pintype "passive"))
      (node (ref "R20") (pin "2") (pinfunction "2_2") (pintype "passive"))
      (node (ref "R37") (pin "1") (pinfunction "1_1") (pintype "passive"))
      (node (ref "U4A") (pin "1") (pinfunction "OUT_1") (pintype "passive"))
      (node (ref "U4A") (pin "2") (pinfunction "-_2") (pintype "passive"))
    )
    (net (code "42") (name "Net-(U4B-+)") (class "Default")
      (node (ref "C34") (pin "2") (pinfunction "2_2") (pintype "passive"))
      (node (ref "U4B") (pin "3") (pinfunction "+_3") (pintype "passive"))
      (node (ref "U7B") (pin "5") (pinfunction "OUT_5") (pintype "passive"))
    )
    (net (code "43") (name "Net-(U4B--)") (class "Default")
      (node (ref "C23") (pin "1") (pinfunction "1_1") (pintype "passive"))
      (node (ref "R19") (pin "2") (pinfunction "2_2") (pintype "passive"))
      (node (ref "R36") (pin "2") (pinfunction "2_2") (pintype "passive"))
      (node (ref "U4B") (pin "1") (pinfunction "OUT_1") (pintype "passive"))
      (node (ref "U4B") (pin "2") (pinfunction "-_2") (pintype "passive"))
    )
    (net (code "44") (name "Net-(U4C--)") (class "Default")
      (node (ref "R45") (pin "2") (pinfunction "2_2") (pintype "passive"))
      (node (ref "R46") (pin "1") (pinfunction "1_1") (pintype "passive"))
      (node (ref "R49") (pin "2") (pinfunction "2_2") (pintype "passive"))
      (node (ref "U4C") (pin "2") (pinfunction "-_2") (pintype "passive"))
    )
    (net (code "45") (name "Net-(U4C-OUT)") (class "Default")
      (node (ref "R46") (pin "2") (pinfunction "2_2") (pintype "passive"))
      (node (ref "R50") (pin "1") (pinfunction "1_1") (pintype "passive"))
      (node (ref "U4C") (pin "1") (pinfunction "OUT_1") (pintype "passive"))
    )
    (net (code "46") (name "Net-(U4D-+)") (class "Default")
      (node (ref "R55") (pin "2") (pinfunction "2_2") (pintype "passive"))
      (node (ref "R56") (pin "1") (pinfunction "1_1") (pintype "passive"))
      (node (ref "U4D") (pin "3") (pinfunction "+_3") (pintype "passive"))
    )
    (net (code "47") (name "Net-(U4D--)") (class "Default")
      (node (ref "R48") (pin "1") (pinfunction "1_1") (pintype "passive"))
      (node (ref "R50") (pin "2") (pinfunction "2_2") (pintype "passive"))
      (node (ref "U4D") (pin "2") (pinfunction "-_2") (pintype "passive"))
    )
    (net (code "48") (name "Net-(U4D-OUT)") (class "Default")
      (node (ref "R47") (pin "2") (pinfunction "2_2") (pintype "passive"))
      (node (ref "R48") (pin "2") (pinfunction "2_2") (pintype "passive"))
      (node (ref "U4D") (pin "1") (pinfunction "OUT_1") (pintype "passive"))
    )
    (net (code "49") (name "Net-(U5A--)") (class "Default")
      (node (ref "R53") (pin "1") (pinfunction "1_1") (pintype "passive"))
      (node (ref "R54") (pin "2") (pinfunction "2_2") (pintype "passive"))
      (node (ref "R58") (pin "2") (pinfunction "2_2") (pintype "passive"))
      (node (ref "R62") (pin "2") (pinfunction "2_2") (pintype "passive"))
      (node (ref "U5A") (pin "2") (pinfunction "-_2") (pintype "passive"))
    )
    (net (code "50") (name "Net-(U7A--)") (class "Default")
      (node (ref "R30") (pin "1") (pinfunction "1_1") (pintype "passive"))
      (node (ref "R31") (pin "1") (pinfunction "1_1") (pintype "passive"))
      (node (ref "R36") (pin "1") (pinfunction "1_1") (pintype "passive"))
      (node (ref "R37") (pin "2") (pinfunction "2_2") (pintype "passive"))
      (node (ref "U7A") (pin "4") (pinfunction "-_4") (pintype "passive"))
    )
    (net (code "51") (name "Net-(U7A-BIAS)") (class "Default")
      (node (ref "R51") (pin "2") (pinfunction "2_2") (pintype "passive"))
      (node (ref "U7A") (pin "1") (pinfunction "BIAS_1") (pintype "passive"))
    )
    (net (code "52") (name "Net-(U7B--)") (class "Default")
      (node (ref "R18") (pin "2") (pinfunction "2_2") (pintype "passive"))
      (node (ref "R19") (pin "1") (pinfunction "1_1") (pintype "passive"))
      (node (ref "R32") (pin "1") (pinfunction "1_1") (pintype "passive"))
      (node (ref "R33") (pin "1") (pinfunction "1_1") (pintype "passive"))
      (node (ref "R34") (pin "1") (pinfunction "1_1") (pintype "passive"))
      (node (ref "U7B") (pin "4") (pinfunction "-_4") (pintype "passive"))
    )
    (net (code "53") (name "Net-(U7B-BIAS)") (class "Default")
      (node (ref "R52") (pin "2") (pinfunction "2_2") (pintype "passive"))
      (node (ref "U7B") (pin "1") (pinfunction "BIAS_1") (pintype "passive"))
    )
    (net (code "54") (name "Net-(U8A--)") (class "Default")
      (node (ref "R35") (pin "2") (pinfunction "2_2") (pintype "passive"))
      (node (ref "R41") (pin "1") (pinfunction "1_1") (pintype "passive"))
      (node (ref "U8A") (pin "4") (pinfunction "-_4") (pintype "passive"))
    )
    (net (code "55") (name "Net-(U8A-BIAS)") (class "Default")
      (node (ref "R47") (pin "1") (pinfunction "1_1") (pintype "passive"))
      (node (ref "U8A") (pin "1") (pinfunction "BIAS_1") (pintype "passive"))
    )
    (net (code "56") (name "Net-(U8A-OUT)") (class "Default")
      (node (ref "R42") (pin "1") (pinfunction "1_1") (pintype "passive"))
      (node (ref "U8A") (pin "5") (pinfunction "OUT_5") (pintype "passive"))
      (node (ref "U8C") (pin "1") (pinfunction "BIN_1") (pintype "passive"))
    )
    (net (code "57") (name "Net-(U8C-V+)") (class "Default")
      (node (ref "R34") (pin "2") (pinfunction "2_2") (pintype "passive"))
      (node (ref "R40") (pin "2") (pinfunction "2_2") (pintype "passive"))
      (node (ref "U8C") (pin "2") (pinfunction "V+_2") (pintype "passive"))
    )
    (net (code "58") (name "unconnected-(U8A-Pad2)") (class "Default")
      (node (ref "U8A") (pin "2") (pinfunction "2_2") (pintype "passive+no_connect"))
    )
  )
)
